# MDM_V3_LEDPad_A.net
KiCad netlist of a schematic drawn in EAGLE
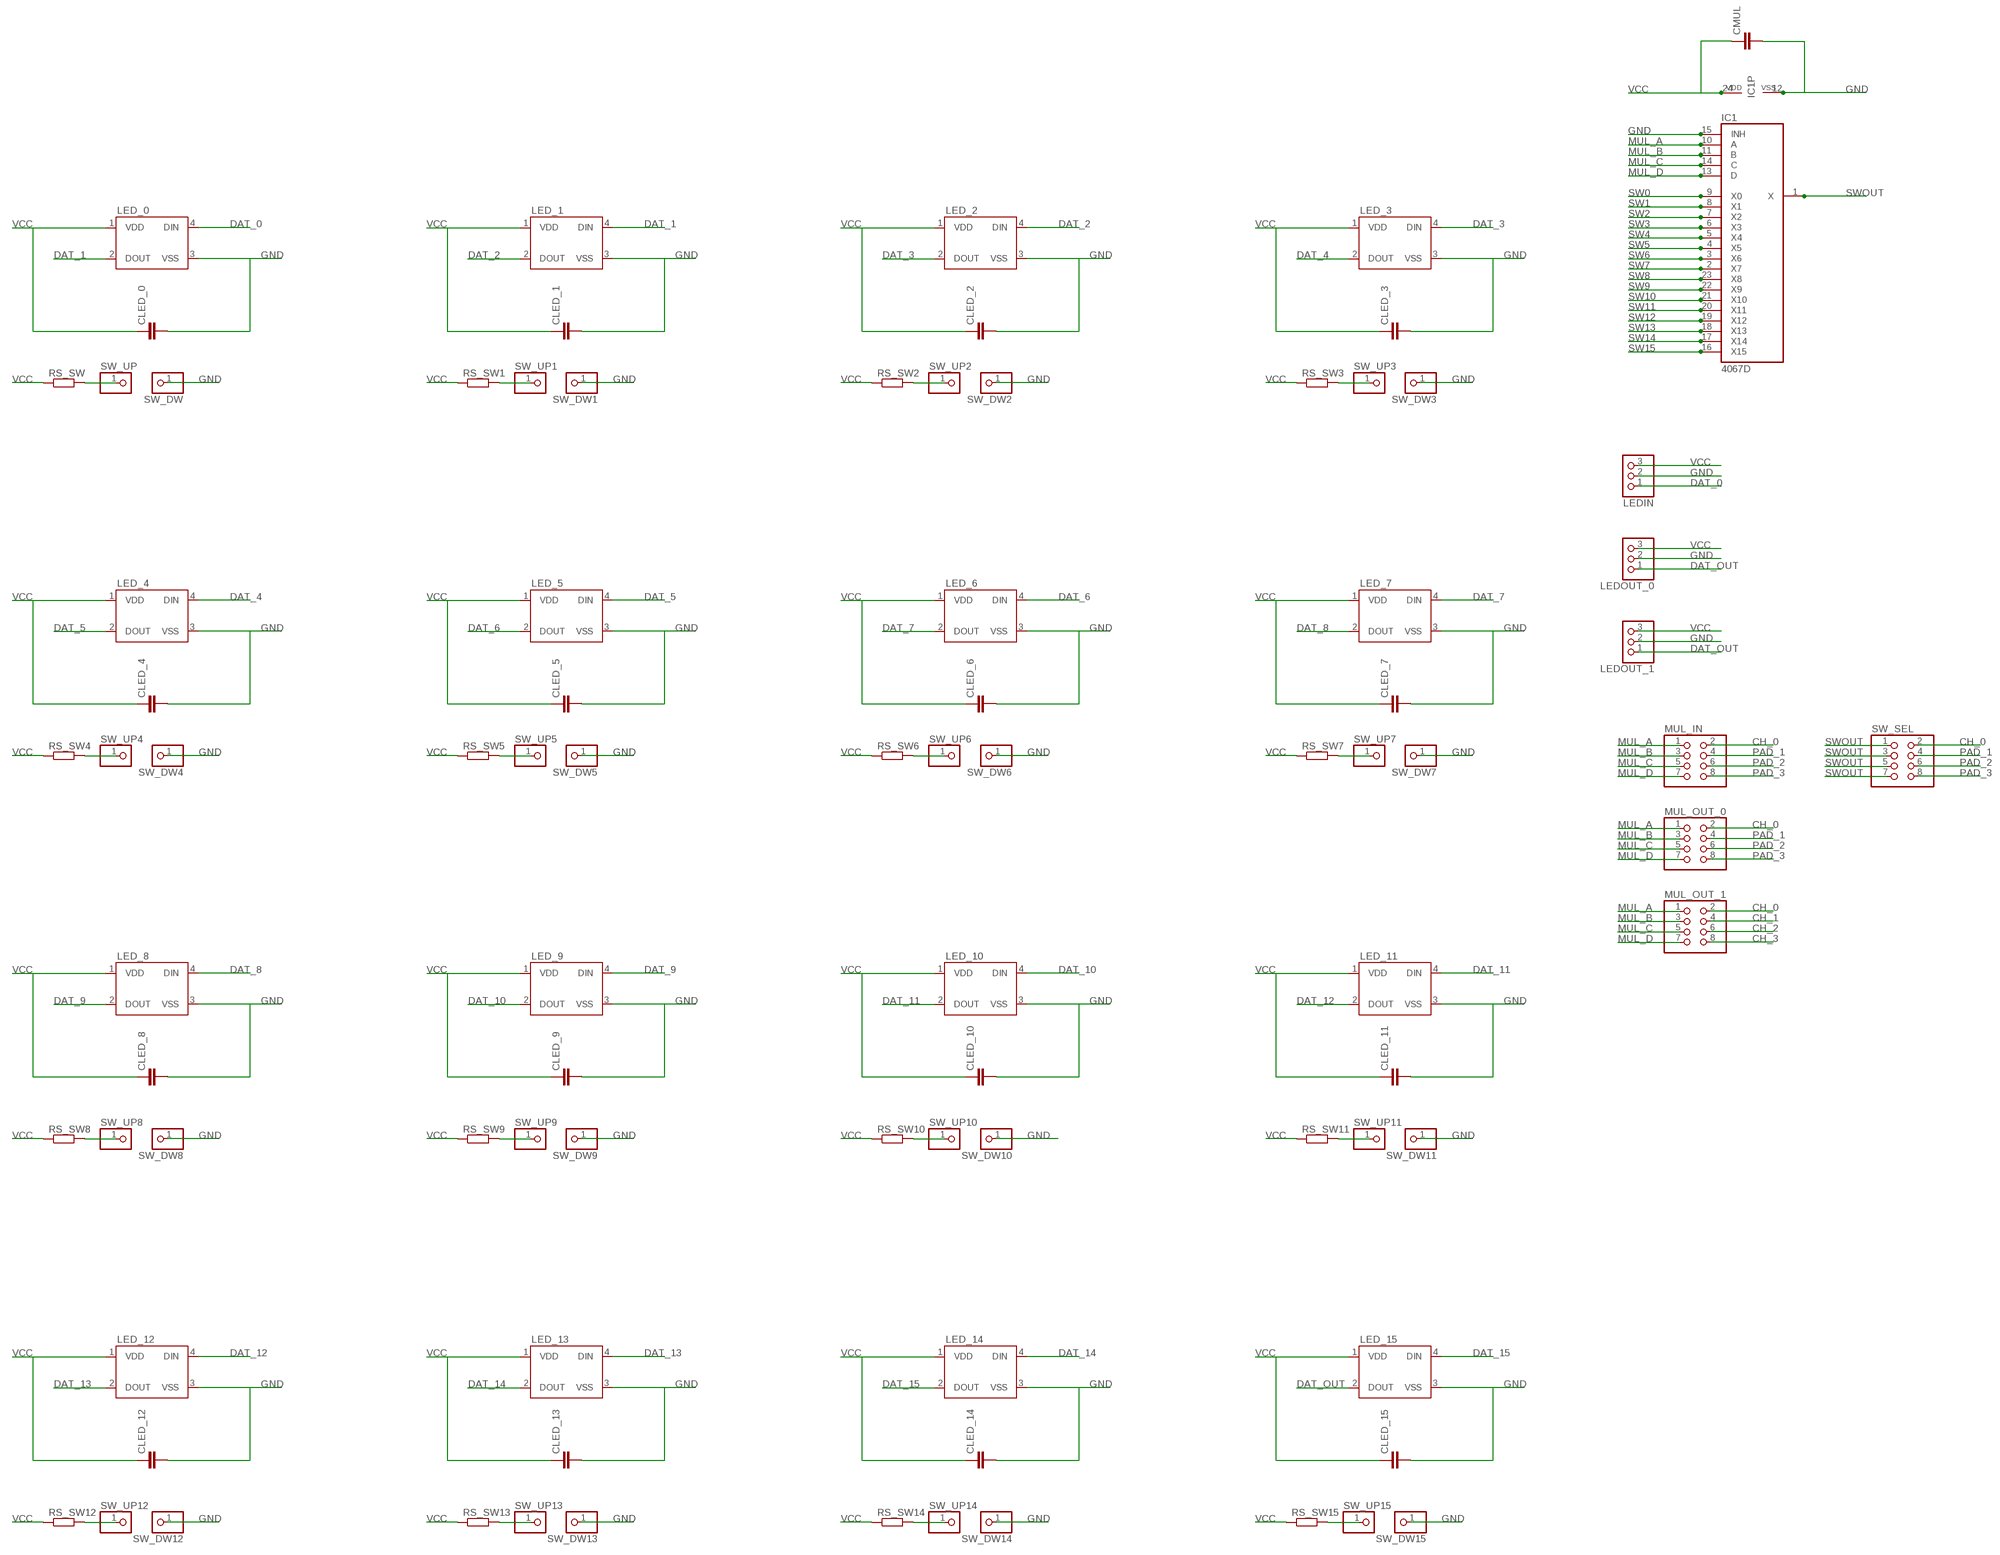
[diagram p0: schematic, sheet 1]

(export (version "E")
  (design (tool "Eeschema 10.0.6"))
  (components
    (comp (ref "CLED_0")
      (value "C-EUC1206K")
      (footprint "eagle-import:C1206K")
      (libsource (lib "eagle-import") (part "C-EUC1206K"))
    )
    (comp (ref "CLED_1")
      (value "C-EUC1206K")
      (footprint "eagle-import:C1206K")
      (libsource (lib "eagle-import") (part "C-EUC1206K"))
    )
    (comp (ref "CLED_2")
      (value "C-EUC1206K")
      (footprint "eagle-import:C1206K")
      (libsource (lib "eagle-import") (part "C-EUC1206K"))
    )
    (comp (ref "CLED_3")
      (value "C-EUC1206K")
      (footprint "eagle-import:C1206K")
      (libsource (lib "eagle-import") (part "C-EUC1206K"))
    )
    (comp (ref "CLED_4")
      (value "C-EUC1206K")
      (footprint "eagle-import:C1206K")
      (libsource (lib "eagle-import") (part "C-EUC1206K"))
    )
    (comp (ref "CLED_5")
      (value "C-EUC1206K")
      (footprint "eagle-import:C1206K")
      (libsource (lib "eagle-import") (part "C-EUC1206K"))
    )
    (comp (ref "CLED_6")
      (value "C-EUC1206K")
      (footprint "eagle-import:C1206K")
      (libsource (lib "eagle-import") (part "C-EUC1206K"))
    )
    (comp (ref "CLED_7")
      (value "C-EUC1206K")
      (footprint "eagle-import:C1206K")
      (libsource (lib "eagle-import") (part "C-EUC1206K"))
    )
    (comp (ref "CLED_8")
      (value "C-EUC1206K")
      (footprint "eagle-import:C1206K")
      (libsource (lib "eagle-import") (part "C-EUC1206K"))
    )
    (comp (ref "CLED_9")
      (value "C-EUC1206K")
      (footprint "eagle-import:C1206K")
      (libsource (lib "eagle-import") (part "C-EUC1206K"))
    )
    (comp (ref "CLED_10")
      (value "C-EUC1206K")
      (footprint "eagle-import:C1206K")
      (libsource (lib "eagle-import") (part "C-EUC1206K"))
    )
    (comp (ref "CLED_11")
      (value "C-EUC1206K")
      (footprint "eagle-import:C1206K")
      (libsource (lib "eagle-import") (part "C-EUC1206K"))
    )
    (comp (ref "CLED_12")
      (value "C-EUC1206K")
      (footprint "eagle-import:C1206K")
      (libsource (lib "eagle-import") (part "C-EUC1206K"))
    )
    (comp (ref "CLED_13")
      (value "C-EUC1206K")
      (footprint "eagle-import:C1206K")
      (libsource (lib "eagle-import") (part "C-EUC1206K"))
    )
    (comp (ref "CLED_14")
      (value "C-EUC1206K")
      (footprint "eagle-import:C1206K")
      (libsource (lib "eagle-import") (part "C-EUC1206K"))
    )
    (comp (ref "CLED_15")
      (value "C-EUC1206K")
      (footprint "eagle-import:C1206K")
      (libsource (lib "eagle-import") (part "C-EUC1206K"))
    )
    (comp (ref "CMUL")
      (value "C-EUC1206K")
      (footprint "eagle-import:C1206K")
      (libsource (lib "eagle-import") (part "C-EUC1206K"))
    )
    (comp (ref "IC1")
      (value "4067D")
      (footprint "eagle-import:SO24W")
      (libsource (lib "eagle-import") (part "4067D"))
    )
    (comp (ref "LEDIN")
      (value "PINHD-1X3")
      (footprint "eagle-import:1X03")
      (libsource (lib "eagle-import") (part "PINHD-1X3"))
    )
    (comp (ref "LEDOUT_0")
      (value "PINHD-1X3")
      (footprint "eagle-import:1X03")
      (libsource (lib "eagle-import") (part "PINHD-1X3"))
    )
    (comp (ref "LEDOUT_1")
      (value "PINHD-1X3")
      (footprint "eagle-import:1X03")
      (libsource (lib "eagle-import") (part "PINHD-1X3"))
    )
    (comp (ref "LED_0")
      (value "WS2812B")
      (footprint "eagle-import:WS2812B")
      (libsource (lib "eagle-import") (part "WS2812B"))
    )
    (comp (ref "LED_1")
      (value "WS2812B")
      (footprint "eagle-import:WS2812B")
      (libsource (lib "eagle-import") (part "WS2812B"))
    )
    (comp (ref "LED_2")
      (value "WS2812B")
      (footprint "eagle-import:WS2812B")
      (libsource (lib "eagle-import") (part "WS2812B"))
    )
    (comp (ref "LED_3")
      (value "WS2812B")
      (footprint "eagle-import:WS2812B")
      (libsource (lib "eagle-import") (part "WS2812B"))
    )
    (comp (ref "LED_4")
      (value "WS2812B")
      (footprint "eagle-import:WS2812B")
      (libsource (lib "eagle-import") (part "WS2812B"))
    )
    (comp (ref "LED_5")
      (value "WS2812B")
      (footprint "eagle-import:WS2812B")
      (libsource (lib "eagle-import") (part "WS2812B"))
    )
    (comp (ref "LED_6")
      (value "WS2812B")
      (footprint "eagle-import:WS2812B")
      (libsource (lib "eagle-import") (part "WS2812B"))
    )
    (comp (ref "LED_7")
      (value "WS2812B")
      (footprint "eagle-import:WS2812B")
      (libsource (lib "eagle-import") (part "WS2812B"))
    )
    (comp (ref "LED_8")
      (value "WS2812B")
      (footprint "eagle-import:WS2812B")
      (libsource (lib "eagle-import") (part "WS2812B"))
    )
    (comp (ref "LED_9")
      (value "WS2812B")
      (footprint "eagle-import:WS2812B")
      (libsource (lib "eagle-import") (part "WS2812B"))
    )
    (comp (ref "LED_10")
      (value "WS2812B")
      (footprint "eagle-import:WS2812B")
      (libsource (lib "eagle-import") (part "WS2812B"))
    )
    (comp (ref "LED_11")
      (value "WS2812B")
      (footprint "eagle-import:WS2812B")
      (libsource (lib "eagle-import") (part "WS2812B"))
    )
    (comp (ref "LED_12")
      (value "WS2812B")
      (footprint "eagle-import:WS2812B")
      (libsource (lib "eagle-import") (part "WS2812B"))
    )
    (comp (ref "LED_13")
      (value "WS2812B")
      (footprint "eagle-import:WS2812B")
      (libsource (lib "eagle-import") (part "WS2812B"))
    )
    (comp (ref "LED_14")
      (value "WS2812B")
      (footprint "eagle-import:WS2812B")
      (libsource (lib "eagle-import") (part "WS2812B"))
    )
    (comp (ref "LED_15")
      (value "WS2812B")
      (footprint "eagle-import:WS2812B")
      (libsource (lib "eagle-import") (part "WS2812B"))
    )
    (comp (ref "MUL_IN")
      (value "PINHD-2X4")
      (footprint "eagle-import:2X04")
      (libsource (lib "eagle-import") (part "PINHD-2X4"))
    )
    (comp (ref "MUL_OUT_0")
      (value "PINHD-2X4")
      (footprint "eagle-import:2X04")
      (libsource (lib "eagle-import") (part "PINHD-2X4"))
    )
    (comp (ref "MUL_OUT_1")
      (value "PINHD-2X4")
      (footprint "eagle-import:2X04")
      (libsource (lib "eagle-import") (part "PINHD-2X4"))
    )
    (comp (ref "RS_SW")
      (value "R-EU_R1206")
      (footprint "eagle-import:R1206")
      (libsource (lib "eagle-import") (part "R-EU_R1206"))
    )
    (comp (ref "RS_SW1")
      (value "R-EU_R1206")
      (footprint "eagle-import:R1206")
      (libsource (lib "eagle-import") (part "R-EU_R1206"))
    )
    (comp (ref "RS_SW2")
      (value "R-EU_R1206")
      (footprint "eagle-import:R1206")
      (libsource (lib "eagle-import") (part "R-EU_R1206"))
    )
    (comp (ref "RS_SW3")
      (value "R-EU_R1206")
      (footprint "eagle-import:R1206")
      (libsource (lib "eagle-import") (part "R-EU_R1206"))
    )
    (comp (ref "RS_SW4")
      (value "R-EU_R1206")
      (footprint "eagle-import:R1206")
      (libsource (lib "eagle-import") (part "R-EU_R1206"))
    )
    (comp (ref "RS_SW5")
      (value "R-EU_R1206")
      (footprint "eagle-import:R1206")
      (libsource (lib "eagle-import") (part "R-EU_R1206"))
    )
    (comp (ref "RS_SW6")
      (value "R-EU_R1206")
      (footprint "eagle-import:R1206")
      (libsource (lib "eagle-import") (part "R-EU_R1206"))
    )
    (comp (ref "RS_SW7")
      (value "R-EU_R1206")
      (footprint "eagle-import:R1206")
      (libsource (lib "eagle-import") (part "R-EU_R1206"))
    )
    (comp (ref "RS_SW8")
      (value "R-EU_R1206")
      (footprint "eagle-import:R1206")
      (libsource (lib "eagle-import") (part "R-EU_R1206"))
    )
    (comp (ref "RS_SW9")
      (value "R-EU_R1206")
      (footprint "eagle-import:R1206")
      (libsource (lib "eagle-import") (part "R-EU_R1206"))
    )
    (comp (ref "RS_SW10")
      (value "R-EU_R1206")
      (footprint "eagle-import:R1206")
      (libsource (lib "eagle-import") (part "R-EU_R1206"))
    )
    (comp (ref "RS_SW11")
      (value "R-EU_R1206")
      (footprint "eagle-import:R1206")
      (libsource (lib "eagle-import") (part "R-EU_R1206"))
    )
    (comp (ref "RS_SW12")
      (value "R-EU_R1206")
      (footprint "eagle-import:R1206")
      (libsource (lib "eagle-import") (part "R-EU_R1206"))
    )
    (comp (ref "RS_SW13")
      (value "R-EU_R1206")
      (footprint "eagle-import:R1206")
      (libsource (lib "eagle-import") (part "R-EU_R1206"))
    )
    (comp (ref "RS_SW14")
      (value "R-EU_R1206")
      (footprint "eagle-import:R1206")
      (libsource (lib "eagle-import") (part "R-EU_R1206"))
    )
    (comp (ref "RS_SW15")
      (value "R-EU_R1206")
      (footprint "eagle-import:R1206")
      (libsource (lib "eagle-import") (part "R-EU_R1206"))
    )
    (comp (ref "SW_DW")
      (value "PINHD-1X1CB")
      (footprint "eagle-import:1X01-CLEANBIG")
      (libsource (lib "eagle-import") (part "PINHD-1X1CB"))
    )
    (comp (ref "SW_DW1")
      (value "PINHD-1X1CB")
      (footprint "eagle-import:1X01-CLEANBIG")
      (libsource (lib "eagle-import") (part "PINHD-1X1CB"))
    )
    (comp (ref "SW_DW2")
      (value "PINHD-1X1CB")
      (footprint "eagle-import:1X01-CLEANBIG")
      (libsource (lib "eagle-import") (part "PINHD-1X1CB"))
    )
    (comp (ref "SW_DW3")
      (value "PINHD-1X1CB")
      (footprint "eagle-import:1X01-CLEANBIG")
      (libsource (lib "eagle-import") (part "PINHD-1X1CB"))
    )
    (comp (ref "SW_DW4")
      (value "PINHD-1X1CB")
      (footprint "eagle-import:1X01-CLEANBIG")
      (libsource (lib "eagle-import") (part "PINHD-1X1CB"))
    )
    (comp (ref "SW_DW5")
      (value "PINHD-1X1CB")
      (footprint "eagle-import:1X01-CLEANBIG")
      (libsource (lib "eagle-import") (part "PINHD-1X1CB"))
    )
    (comp (ref "SW_DW6")
      (value "PINHD-1X1CB")
      (footprint "eagle-import:1X01-CLEANBIG")
      (libsource (lib "eagle-import") (part "PINHD-1X1CB"))
    )
    (comp (ref "SW_DW7")
      (value "PINHD-1X1CB")
      (footprint "eagle-import:1X01-CLEANBIG")
      (libsource (lib "eagle-import") (part "PINHD-1X1CB"))
    )
    (comp (ref "SW_DW8")
      (value "PINHD-1X1CB")
      (footprint "eagle-import:1X01-CLEANBIG")
      (libsource (lib "eagle-import") (part "PINHD-1X1CB"))
    )
    (comp (ref "SW_DW9")
      (value "PINHD-1X1CB")
      (footprint "eagle-import:1X01-CLEANBIG")
      (libsource (lib "eagle-import") (part "PINHD-1X1CB"))
    )
    (comp (ref "SW_DW10")
      (value "PINHD-1X1CB")
      (footprint "eagle-import:1X01-CLEANBIG")
      (libsource (lib "eagle-import") (part "PINHD-1X1CB"))
    )
    (comp (ref "SW_DW11")
      (value "PINHD-1X1CB")
      (footprint "eagle-import:1X01-CLEANBIG")
      (libsource (lib "eagle-import") (part "PINHD-1X1CB"))
    )
    (comp (ref "SW_DW12")
      (value "PINHD-1X1CB")
      (footprint "eagle-import:1X01-CLEANBIG")
      (libsource (lib "eagle-import") (part "PINHD-1X1CB"))
    )
    (comp (ref "SW_DW13")
      (value "PINHD-1X1CB")
      (footprint "eagle-import:1X01-CLEANBIG")
      (libsource (lib "eagle-import") (part "PINHD-1X1CB"))
    )
    (comp (ref "SW_DW14")
      (value "PINHD-1X1CB")
      (footprint "eagle-import:1X01-CLEANBIG")
      (libsource (lib "eagle-import") (part "PINHD-1X1CB"))
    )
    (comp (ref "SW_DW15")
      (value "PINHD-1X1CB")
      (footprint "eagle-import:1X01-CLEANBIG")
      (libsource (lib "eagle-import") (part "PINHD-1X1CB"))
    )
    (comp (ref "SW_SEL")
      (value "PINHD-2X4")
      (footprint "eagle-import:2X04")
      (libsource (lib "eagle-import") (part "PINHD-2X4"))
    )
    (comp (ref "SW_UP")
      (value "PINHD-1X1CB")
      (footprint "eagle-import:1X01-CLEANBIG")
      (libsource (lib "eagle-import") (part "PINHD-1X1CB"))
    )
    (comp (ref "SW_UP1")
      (value "PINHD-1X1CB")
      (footprint "eagle-import:1X01-CLEANBIG")
      (libsource (lib "eagle-import") (part "PINHD-1X1CB"))
    )
    (comp (ref "SW_UP2")
      (value "PINHD-1X1CB")
      (footprint "eagle-import:1X01-CLEANBIG")
      (libsource (lib "eagle-import") (part "PINHD-1X1CB"))
    )
    (comp (ref "SW_UP3")
      (value "PINHD-1X1CB")
      (footprint "eagle-import:1X01-CLEANBIG")
      (libsource (lib "eagle-import") (part "PINHD-1X1CB"))
    )
    (comp (ref "SW_UP4")
      (value "PINHD-1X1CB")
      (footprint "eagle-import:1X01-CLEANBIG")
      (libsource (lib "eagle-import") (part "PINHD-1X1CB"))
    )
    (comp (ref "SW_UP5")
      (value "PINHD-1X1CB")
      (footprint "eagle-import:1X01-CLEANBIG")
      (libsource (lib "eagle-import") (part "PINHD-1X1CB"))
    )
    (comp (ref "SW_UP6")
      (value "PINHD-1X1CB")
      (footprint "eagle-import:1X01-CLEANBIG")
      (libsource (lib "eagle-import") (part "PINHD-1X1CB"))
    )
    (comp (ref "SW_UP7")
      (value "PINHD-1X1CB")
      (footprint "eagle-import:1X01-CLEANBIG")
      (libsource (lib "eagle-import") (part "PINHD-1X1CB"))
    )
    (comp (ref "SW_UP8")
      (value "PINHD-1X1CB")
      (footprint "eagle-import:1X01-CLEANBIG")
      (libsource (lib "eagle-import") (part "PINHD-1X1CB"))
    )
    (comp (ref "SW_UP9")
      (value "PINHD-1X1CB")
      (footprint "eagle-import:1X01-CLEANBIG")
      (libsource (lib "eagle-import") (part "PINHD-1X1CB"))
    )
    (comp (ref "SW_UP10")
      (value "PINHD-1X1CB")
      (footprint "eagle-import:1X01-CLEANBIG")
      (libsource (lib "eagle-import") (part "PINHD-1X1CB"))
    )
    (comp (ref "SW_UP11")
      (value "PINHD-1X1CB")
      (footprint "eagle-import:1X01-CLEANBIG")
      (libsource (lib "eagle-import") (part "PINHD-1X1CB"))
    )
    (comp (ref "SW_UP12")
      (value "PINHD-1X1CB")
      (footprint "eagle-import:1X01-CLEANBIG")
      (libsource (lib "eagle-import") (part "PINHD-1X1CB"))
    )
    (comp (ref "SW_UP13")
      (value "PINHD-1X1CB")
      (footprint "eagle-import:1X01-CLEANBIG")
      (libsource (lib "eagle-import") (part "PINHD-1X1CB"))
    )
    (comp (ref "SW_UP14")
      (value "PINHD-1X1CB")
      (footprint "eagle-import:1X01-CLEANBIG")
      (libsource (lib "eagle-import") (part "PINHD-1X1CB"))
    )
    (comp (ref "SW_UP15")
      (value "PINHD-1X1CB")
      (footprint "eagle-import:1X01-CLEANBIG")
      (libsource (lib "eagle-import") (part "PINHD-1X1CB"))
    )
  )
  (nets
    (net (code "1") (name "/CH_0") (class "Default")
      (node (ref "MUL_IN") (pin "2") (pinfunction "2_2") (pintype "passive"))
      (node (ref "MUL_OUT_0") (pin "2") (pinfunction "2_2") (pintype "passive"))
      (node (ref "MUL_OUT_1") (pin "2") (pinfunction "2_2") (pintype "passive"))
      (node (ref "SW_SEL") (pin "2") (pinfunction "2_2") (pintype "passive"))
    )
    (net (code "2") (name "/CH_1") (class "Default")
      (node (ref "MUL_OUT_1") (pin "4") (pinfunction "4_4") (pintype "passive"))
    )
    (net (code "3") (name "/CH_2") (class "Default")
      (node (ref "MUL_OUT_1") (pin "6") (pinfunction "6_6") (pintype "passive"))
    )
    (net (code "4") (name "/CH_3") (class "Default")
      (node (ref "MUL_OUT_1") (pin "8") (pinfunction "8_8") (pintype "passive"))
    )
    (net (code "5") (name "/DAT_0") (class "Default")
      (node (ref "LEDIN") (pin "1") (pinfunction "1_1") (pintype "passive"))
      (node (ref "LED_0") (pin "4") (pinfunction "DIN_4") (pintype "input"))
    )
    (net (code "6") (name "/DAT_1") (class "Default")
      (node (ref "LED_0") (pin "2") (pinfunction "DOUT_2") (pintype "output"))
      (node (ref "LED_1") (pin "4") (pinfunction "DIN_4") (pintype "input"))
    )
    (net (code "7") (name "/DAT_2") (class "Default")
      (node (ref "LED_1") (pin "2") (pinfunction "DOUT_2") (pintype "output"))
      (node (ref "LED_2") (pin "4") (pinfunction "DIN_4") (pintype "input"))
    )
    (net (code "8") (name "/DAT_3") (class "Default")
      (node (ref "LED_2") (pin "2") (pinfunction "DOUT_2") (pintype "output"))
      (node (ref "LED_3") (pin "4") (pinfunction "DIN_4") (pintype "input"))
    )
    (net (code "9") (name "/DAT_4") (class "Default")
      (node (ref "LED_3") (pin "2") (pinfunction "DOUT_2") (pintype "output"))
      (node (ref "LED_4") (pin "4") (pinfunction "DIN_4") (pintype "input"))
    )
    (net (code "10") (name "/DAT_5") (class "Default")
      (node (ref "LED_4") (pin "2") (pinfunction "DOUT_2") (pintype "output"))
      (node (ref "LED_5") (pin "4") (pinfunction "DIN_4") (pintype "input"))
    )
    (net (code "11") (name "/DAT_6") (class "Default")
      (node (ref "LED_5") (pin "2") (pinfunction "DOUT_2") (pintype "output"))
      (node (ref "LED_6") (pin "4") (pinfunction "DIN_4") (pintype "input"))
    )
    (net (code "12") (name "/DAT_7") (class "Default")
      (node (ref "LED_6") (pin "2") (pinfunction "DOUT_2") (pintype "output"))
      (node (ref "LED_7") (pin "4") (pinfunction "DIN_4") (pintype "input"))
    )
    (net (code "13") (name "/DAT_8") (class "Default")
      (node (ref "LED_7") (pin "2") (pinfunction "DOUT_2") (pintype "output"))
      (node (ref "LED_8") (pin "4") (pinfunction "DIN_4") (pintype "input"))
    )
    (net (code "14") (name "/DAT_9") (class "Default")
      (node (ref "LED_8") (pin "2") (pinfunction "DOUT_2") (pintype "output"))
      (node (ref "LED_9") (pin "4") (pinfunction "DIN_4") (pintype "input"))
    )
    (net (code "15") (name "/DAT_10") (class "Default")
      (node (ref "LED_10") (pin "4") (pinfunction "DIN_4") (pintype "input"))
      (node (ref "LED_9") (pin "2") (pinfunction "DOUT_2") (pintype "output"))
    )
    (net (code "16") (name "/DAT_11") (class "Default")
      (node (ref "LED_10") (pin "2") (pinfunction "DOUT_2") (pintype "output"))
      (node (ref "LED_11") (pin "4") (pinfunction "DIN_4") (pintype "input"))
    )
    (net (code "17") (name "/DAT_12") (class "Default")
      (node (ref "LED_11") (pin "2") (pinfunction "DOUT_2") (pintype "output"))
      (node (ref "LED_12") (pin "4") (pinfunction "DIN_4") (pintype "input"))
    )
    (net (code "18") (name "/DAT_13") (class "Default")
      (node (ref "LED_12") (pin "2") (pinfunction "DOUT_2") (pintype "output"))
      (node (ref "LED_13") (pin "4") (pinfunction "DIN_4") (pintype "input"))
    )
    (net (code "19") (name "/DAT_14") (class "Default")
      (node (ref "LED_13") (pin "2") (pinfunction "DOUT_2") (pintype "output"))
      (node (ref "LED_14") (pin "4") (pinfunction "DIN_4") (pintype "input"))
    )
    (net (code "20") (name "/DAT_15") (class "Default")
      (node (ref "LED_14") (pin "2") (pinfunction "DOUT_2") (pintype "output"))
      (node (ref "LED_15") (pin "4") (pinfunction "DIN_4") (pintype "input"))
    )
    (net (code "21") (name "/DAT_OUT") (class "Default")
      (node (ref "LEDOUT_0") (pin "1") (pinfunction "1_1") (pintype "passive"))
      (node (ref "LEDOUT_1") (pin "1") (pinfunction "1_1") (pintype "passive"))
      (node (ref "LED_15") (pin "2") (pinfunction "DOUT_2") (pintype "output"))
    )
    (net (code "22") (name "/GND") (class "Default")
      (node (ref "CLED_0") (pin "2") (pinfunction "2_2") (pintype "passive"))
      (node (ref "CLED_1") (pin "2") (pinfunction "2_2") (pintype "passive"))
      (node (ref "CLED_10") (pin "2") (pinfunction "2_2") (pintype "passive"))
      (node (ref "CLED_11") (pin "2") (pinfunction "2_2") (pintype "passive"))
      (node (ref "CLED_12") (pin "2") (pinfunction "2_2") (pintype "passive"))
      (node (ref "CLED_13") (pin "2") (pinfunction "2_2") (pintype "passive"))
      (node (ref "CLED_14") (pin "2") (pinfunction "2_2") (pintype "passive"))
      (node (ref "CLED_15") (pin "2") (pinfunction "2_2") (pintype "passive"))
      (node (ref "CLED_2") (pin "2") (pinfunction "2_2") (pintype "passive"))
      (node (ref "CLED_3") (pin "2") (pinfunction "2_2") (pintype "passive"))
      (node (ref "CLED_4") (pin "2") (pinfunction "2_2") (pintype "passive"))
      (node (ref "CLED_5") (pin "2") (pinfunction "2_2") (pintype "passive"))
      (node (ref "CLED_6") (pin "2") (pinfunction "2_2") (pintype "passive"))
      (node (ref "CLED_7") (pin "2") (pinfunction "2_2") (pintype "passive"))
      (node (ref "CLED_8") (pin "2") (pinfunction "2_2") (pintype "passive"))
      (node (ref "CLED_9") (pin "2") (pinfunction "2_2") (pintype "passive"))
      (node (ref "CMUL") (pin "2") (pinfunction "2_2") (pintype "passive"))
      (node (ref "IC1") (pin "12") (pinfunction "VSS_12") (pintype "power_in"))
      (node (ref "IC1") (pin "15") (pinfunction "INH_15") (pintype "input"))
      (node (ref "LEDIN") (pin "2") (pinfunction "2_2") (pintype "passive"))
      (node (ref "LEDOUT_0") (pin "2") (pinfunction "2_2") (pintype "passive"))
      (node (ref "LEDOUT_1") (pin "2") (pinfunction "2_2") (pintype "passive"))
      (node (ref "LED_0") (pin "3") (pinfunction "VSS_3") (pintype "power_in"))
      (node (ref "LED_1") (pin "3") (pinfunction "VSS_3") (pintype "power_in"))
      (node (ref "LED_10") (pin "3") (pinfunction "VSS_3") (pintype "power_in"))
      (node (ref "LED_11") (pin "3") (pinfunction "VSS_3") (pintype "power_in"))
      (node (ref "LED_12") (pin "3") (pinfunction "VSS_3") (pintype "power_in"))
      (node (ref "LED_13") (pin "3") (pinfunction "VSS_3") (pintype "power_in"))
      (node (ref "LED_14") (pin "3") (pinfunction "VSS_3") (pintype "power_in"))
      (node (ref "LED_15") (pin "3") (pinfunction "VSS_3") (pintype "power_in"))
      (node (ref "LED_2") (pin "3") (pinfunction "VSS_3") (pintype "power_in"))
      (node (ref "LED_3") (pin "3") (pinfunction "VSS_3") (pintype "power_in"))
      (node (ref "LED_4") (pin "3") (pinfunction "VSS_3") (pintype "power_in"))
      (node (ref "LED_5") (pin "3") (pinfunction "VSS_3") (pintype "power_in"))
      (node (ref "LED_6") (pin "3") (pinfunction "VSS_3") (pintype "power_in"))
      (node (ref "LED_7") (pin "3") (pinfunction "VSS_3") (pintype "power_in"))
      (node (ref "LED_8") (pin "3") (pinfunction "VSS_3") (pintype "power_in"))
      (node (ref "LED_9") (pin "3") (pinfunction "VSS_3") (pintype "power_in"))
      (node (ref "SW_DW") (pin "1") (pinfunction "1_1") (pintype "passive"))
      (node (ref "SW_DW1") (pin "1") (pinfunction "1_1") (pintype "passive"))
      (node (ref "SW_DW10") (pin "1") (pinfunction "1_1") (pintype "passive"))
      (node (ref "SW_DW11") (pin "1") (pinfunction "1_1") (pintype "passive"))
      (node (ref "SW_DW12") (pin "1") (pinfunction "1_1") (pintype "passive"))
      (node (ref "SW_DW13") (pin "1") (pinfunction "1_1") (pintype "passive"))
      (node (ref "SW_DW14") (pin "1") (pinfunction "1_1") (pintype "passive"))
      (node (ref "SW_DW15") (pin "1") (pinfunction "1_1") (pintype "passive"))
      (node (ref "SW_DW2") (pin "1") (pinfunction "1_1") (pintype "passive"))
      (node (ref "SW_DW3") (pin "1") (pinfunction "1_1") (pintype "passive"))
      (node (ref "SW_DW4") (pin "1") (pinfunction "1_1") (pintype "passive"))
      (node (ref "SW_DW5") (pin "1") (pinfunction "1_1") (pintype "passive"))
      (node (ref "SW_DW6") (pin "1") (pinfunction "1_1") (pintype "passive"))
      (node (ref "SW_DW7") (pin "1") (pinfunction "1_1") (pintype "passive"))
      (node (ref "SW_DW8") (pin "1") (pinfunction "1_1") (pintype "passive"))
      (node (ref "SW_DW9") (pin "1") (pinfunction "1_1") (pintype "passive"))
    )
    (net (code "23") (name "/MUL_A") (class "Default")
      (node (ref "IC1") (pin "10") (pinfunction "A_10") (pintype "input"))
      (node (ref "MUL_IN") (pin "1") (pinfunction "1_1") (pintype "passive"))
      (node (ref "MUL_OUT_0") (pin "1") (pinfunction "1_1") (pintype "passive"))
      (node (ref "MUL_OUT_1") (pin "1") (pinfunction "1_1") (pintype "passive"))
    )
    (net (code "24") (name "/MUL_B") (class "Default")
      (node (ref "IC1") (pin "11") (pinfunction "B_11") (pintype "input"))
      (node (ref "MUL_IN") (pin "3") (pinfunction "3_3") (pintype "passive"))
      (node (ref "MUL_OUT_0") (pin "3") (pinfunction "3_3") (pintype "passive"))
      (node (ref "MUL_OUT_1") (pin "3") (pinfunction "3_3") (pintype "passive"))
    )
    (net (code "25") (name "/MUL_C") (class "Default")
      (node (ref "IC1") (pin "14") (pinfunction "C_14") (pintype "input"))
      (node (ref "MUL_IN") (pin "5") (pinfunction "5_5") (pintype "passive"))
      (node (ref "MUL_OUT_0") (pin "5") (pinfunction "5_5") (pintype "passive"))
      (node (ref "MUL_OUT_1") (pin "5") (pinfunction "5_5") (pintype "passive"))
    )
    (net (code "26") (name "/MUL_D") (class "Default")
      (node (ref "IC1") (pin "13") (pinfunction "D_13") (pintype "input"))
      (node (ref "MUL_IN") (pin "7") (pinfunction "7_7") (pintype "passive"))
      (node (ref "MUL_OUT_0") (pin "7") (pinfunction "7_7") (pintype "passive"))
      (node (ref "MUL_OUT_1") (pin "7") (pinfunction "7_7") (pintype "passive"))
    )
    (net (code "27") (name "/PAD_1") (class "Default")
      (node (ref "MUL_IN") (pin "4") (pinfunction "4_4") (pintype "passive"))
      (node (ref "MUL_OUT_0") (pin "4") (pinfunction "4_4") (pintype "passive"))
      (node (ref "SW_SEL") (pin "4") (pinfunction "4_4") (pintype "passive"))
    )
    (net (code "28") (name "/PAD_2") (class "Default")
      (node (ref "MUL_IN") (pin "6") (pinfunction "6_6") (pintype "passive"))
      (node (ref "MUL_OUT_0") (pin "6") (pinfunction "6_6") (pintype "passive"))
      (node (ref "SW_SEL") (pin "6") (pinfunction "6_6") (pintype "passive"))
    )
    (net (code "29") (name "/PAD_3") (class "Default")
      (node (ref "MUL_IN") (pin "8") (pinfunction "8_8") (pintype "passive"))
      (node (ref "MUL_OUT_0") (pin "8") (pinfunction "8_8") (pintype "passive"))
      (node (ref "SW_SEL") (pin "8") (pinfunction "8_8") (pintype "passive"))
    )
    (net (code "30") (name "/SW0") (class "Default")
      (node (ref "IC1") (pin "9") (pinfunction "X0_9") (pintype "input"))
    )
    (net (code "31") (name "/SW1") (class "Default")
      (node (ref "IC1") (pin "8") (pinfunction "X1_8") (pintype "input"))
      (node (ref "RS_SW1") (pin "2") (pinfunction "2_2") (pintype "passive"))
      (node (ref "SW_UP1") (pin "1") (pinfunction "1_1") (pintype "passive"))
    )
    (net (code "32") (name "/SW2") (class "Default")
      (node (ref "IC1") (pin "7") (pinfunction "X2_7") (pintype "input"))
      (node (ref "RS_SW2") (pin "2") (pinfunction "2_2") (pintype "passive"))
      (node (ref "SW_UP2") (pin "1") (pinfunction "1_1") (pintype "passive"))
    )
    (net (code "33") (name "/SW3") (class "Default")
      (node (ref "IC1") (pin "6") (pinfunction "X3_6") (pintype "input"))
      (node (ref "RS_SW3") (pin "2") (pinfunction "2_2") (pintype "passive"))
      (node (ref "SW_UP3") (pin "1") (pinfunction "1_1") (pintype "passive"))
    )
    (net (code "34") (name "/SW4") (class "Default")
      (node (ref "IC1") (pin "5") (pinfunction "X4_5") (pintype "input"))
      (node (ref "RS_SW4") (pin "2") (pinfunction "2_2") (pintype "passive"))
      (node (ref "SW_UP4") (pin "1") (pinfunction "1_1") (pintype "passive"))
    )
    (net (code "35") (name "/SW5") (class "Default")
      (node (ref "IC1") (pin "4") (pinfunction "X5_4") (pintype "input"))
      (node (ref "RS_SW5") (pin "2") (pinfunction "2_2") (pintype "passive"))
      (node (ref "SW_UP5") (pin "1") (pinfunction "1_1") (pintype "passive"))
    )
    (net (code "36") (name "/SW6") (class "Default")
      (node (ref "IC1") (pin "3") (pinfunction "X6_3") (pintype "input"))
      (node (ref "RS_SW6") (pin "2") (pinfunction "2_2") (pintype "passive"))
      (node (ref "SW_UP6") (pin "1") (pinfunction "1_1") (pintype "passive"))
    )
    (net (code "37") (name "/SW7") (class "Default")
      (node (ref "IC1") (pin "2") (pinfunction "X7_2") (pintype "input"))
      (node (ref "RS_SW7") (pin "2") (pinfunction "2_2") (pintype "passive"))
      (node (ref "SW_UP7") (pin "1") (pinfunction "1_1") (pintype "passive"))
    )
    (net (code "38") (name "/SW8") (class "Default")
      (node (ref "IC1") (pin "23") (pinfunction "X8_23") (pintype "input"))
      (node (ref "RS_SW8") (pin "2") (pinfunction "2_2") (pintype "passive"))
      (node (ref "SW_UP8") (pin "1") (pinfunction "1_1") (pintype "passive"))
    )
    (net (code "39") (name "/SW9") (class "Default")
      (node (ref "IC1") (pin "22") (pinfunction "X9_22") (pintype "input"))
      (node (ref "RS_SW9") (pin "2") (pinfunction "2_2") (pintype "passive"))
      (node (ref "SW_UP9") (pin "1") (pinfunction "1_1") (pintype "passive"))
    )
    (net (code "40") (name "/SW10") (class "Default")
      (node (ref "IC1") (pin "21") (pinfunction "X10_21") (pintype "input"))
      (node (ref "RS_SW10") (pin "2") (pinfunction "2_2") (pintype "passive"))
      (node (ref "SW_UP10") (pin "1") (pinfunction "1_1") (pintype "passive"))
    )
    (net (code "41") (name "/SW11") (class "Default")
      (node (ref "IC1") (pin "20") (pinfunction "X11_20") (pintype "input"))
      (node (ref "RS_SW11") (pin "2") (pinfunction "2_2") (pintype "passive"))
      (node (ref "SW_UP11") (pin "1") (pinfunction "1_1") (pintype "passive"))
    )
    (net (code "42") (name "/SW12") (class "Default")
      (node (ref "IC1") (pin "19") (pinfunction "X12_19") (pintype "input"))
      (node (ref "RS_SW12") (pin "2") (pinfunction "2_2") (pintype "passive"))
      (node (ref "SW_UP12") (pin "1") (pinfunction "1_1") (pintype "passive"))
    )
    (net (code "43") (name "/SW13") (class "Default")
      (node (ref "IC1") (pin "18") (pinfunction "X13_18") (pintype "input"))
      (node (ref "RS_SW13") (pin "2") (pinfunction "2_2") (pintype "passive"))
      (node (ref "SW_UP13") (pin "1") (pinfunction "1_1") (pintype "passive"))
    )
    (net (code "44") (name "/SW14") (class "Default")
      (node (ref "IC1") (pin "17") (pinfunction "X14_17") (pintype "input"))
      (node (ref "RS_SW14") (pin "2") (pinfunction "2_2") (pintype "passive"))
      (node (ref "SW_UP14") (pin "1") (pinfunction "1_1") (pintype "passive"))
    )
    (net (code "45") (name "/SW15") (class "Default")
      (node (ref "IC1") (pin "16") (pinfunction "X15_16") (pintype "input"))
      (node (ref "RS_SW15") (pin "2") (pinfunction "2_2") (pintype "passive"))
      (node (ref "SW_UP15") (pin "1") (pinfunction "1_1") (pintype "passive"))
    )
    (net (code "46") (name "/SWOUT") (class "Default")
      (node (ref "IC1") (pin "1") (pinfunction "X_1") (pintype "output"))
      (node (ref "SW_SEL") (pin "1") (pinfunction "1_1") (pintype "passive"))
      (node (ref "SW_SEL") (pin "3") (pinfunction "3_3") (pintype "passive"))
      (node (ref "SW_SEL") (pin "5") (pinfunction "5_5") (pintype "passive"))
      (node (ref "SW_SEL") (pin "7") (pinfunction "7_7") (pintype "passive"))
    )
    (net (code "47") (name "/VCC") (class "Default")
      (node (ref "CLED_0") (pin "1") (pinfunction "1_1") (pintype "passive"))
      (node (ref "CLED_1") (pin "1") (pinfunction "1_1") (pintype "passive"))
      (node (ref "CLED_10") (pin "1") (pinfunction "1_1") (pintype "passive"))
      (node (ref "CLED_11") (pin "1") (pinfunction "1_1") (pintype "passive"))
      (node (ref "CLED_12") (pin "1") (pinfunction "1_1") (pintype "passive"))
      (node (ref "CLED_13") (pin "1") (pinfunction "1_1") (pintype "passive"))
      (node (ref "CLED_14") (pin "1") (pinfunction "1_1") (pintype "passive"))
      (node (ref "CLED_15") (pin "1") (pinfunction "1_1") (pintype "passive"))
      (node (ref "CLED_2") (pin "1") (pinfunction "1_1") (pintype "passive"))
      (node (ref "CLED_3") (pin "1") (pinfunction "1_1") (pintype "passive"))
      (node (ref "CLED_4") (pin "1") (pinfunction "1_1") (pintype "passive"))
      (node (ref "CLED_5") (pin "1") (pinfunction "1_1") (pintype "passive"))
      (node (ref "CLED_6") (pin "1") (pinfunction "1_1") (pintype "passive"))
      (node (ref "CLED_7") (pin "1") (pinfunction "1_1") (pintype "passive"))
      (node (ref "CLED_8") (pin "1") (pinfunction "1_1") (pintype "passive"))
      (node (ref "CLED_9") (pin "1") (pinfunction "1_1") (pintype "passive"))
      (node (ref "CMUL") (pin "1") (pinfunction "1_1") (pintype "passive"))
      (node (ref "IC1") (pin "24") (pinfunction "VDD_24") (pintype "power_in"))
      (node (ref "LEDIN") (pin "3") (pinfunction "3_3") (pintype "passive"))
      (node (ref "LEDOUT_0") (pin "3") (pinfunction "3_3") (pintype "passive"))
      (node (ref "LEDOUT_1") (pin "3") (pinfunction "3_3") (pintype "passive"))
      (node (ref "LED_0") (pin "1") (pinfunction "VDD_1") (pintype "power_in"))
      (node (ref "LED_1") (pin "1") (pinfunction "VDD_1") (pintype "power_in"))
      (node (ref "LED_10") (pin "1") (pinfunction "VDD_1") (pintype "power_in"))
      (node (ref "LED_11") (pin "1") (pinfunction "VDD_1") (pintype "power_in"))
      (node (ref "LED_12") (pin "1") (pinfunction "VDD_1") (pintype "power_in"))
      (node (ref "LED_13") (pin "1") (pinfunction "VDD_1") (pintype "power_in"))
      (node (ref "LED_14") (pin "1") (pinfunction "VDD_1") (pintype "power_in"))
      (node (ref "LED_15") (pin "1") (pinfunction "VDD_1") (pintype "power_in"))
      (node (ref "LED_2") (pin "1") (pinfunction "VDD_1") (pintype "power_in"))
      (node (ref "LED_3") (pin "1") (pinfunction "VDD_1") (pintype "power_in"))
      (node (ref "LED_4") (pin "1") (pinfunction "VDD_1") (pintype "power_in"))
      (node (ref "LED_5") (pin "1") (pinfunction "VDD_1") (pintype "power_in"))
      (node (ref "LED_6") (pin "1") (pinfunction "VDD_1") (pintype "power_in"))
      (node (ref "LED_7") (pin "1") (pinfunction "VDD_1") (pintype "power_in"))
      (node (ref "LED_8") (pin "1") (pinfunction "VDD_1") (pintype "power_in"))
      (node (ref "LED_9") (pin "1") (pinfunction "VDD_1") (pintype "power_in"))
      (node (ref "RS_SW") (pin "1") (pinfunction "1_1") (pintype "passive"))
      (node (ref "RS_SW1") (pin "1") (pinfunction "1_1") (pintype "passive"))
      (node (ref "RS_SW10") (pin "1") (pinfunction "1_1") (pintype "passive"))
      (node (ref "RS_SW11") (pin "1") (pinfunction "1_1") (pintype "passive"))
      (node (ref "RS_SW12") (pin "1") (pinfunction "1_1") (pintype "passive"))
      (node (ref "RS_SW13") (pin "1") (pinfunction "1_1") (pintype "passive"))
      (node (ref "RS_SW14") (pin "1") (pinfunction "1_1") (pintype "passive"))
      (node (ref "RS_SW15") (pin "1") (pinfunction "1_1") (pintype "passive"))
      (node (ref "RS_SW2") (pin "1") (pinfunction "1_1") (pintype "passive"))
      (node (ref "RS_SW3") (pin "1") (pinfunction "1_1") (pintype "passive"))
      (node (ref "RS_SW4") (pin "1") (pinfunction "1_1") (pintype "passive"))
      (node (ref "RS_SW5") (pin "1") (pinfunction "1_1") (pintype "passive"))
      (node (ref "RS_SW6") (pin "1") (pinfunction "1_1") (pintype "passive"))
      (node (ref "RS_SW7") (pin "1") (pinfunction "1_1") (pintype "passive"))
      (node (ref "RS_SW8") (pin "1") (pinfunction "1_1") (pintype "passive"))
      (node (ref "RS_SW9") (pin "1") (pinfunction "1_1") (pintype "passive"))
    )
    (net (code "48") (name "Net-(RS_SW-Pad2)") (class "Default")
      (node (ref "RS_SW") (pin "2") (pinfunction "2_2") (pintype "passive"))
      (node (ref "SW_UP") (pin "1") (pinfunction "1_1") (pintype "passive"))
    )
  )
)
